# LED.net
KiCad netlist of a schematic drawn in Altium Designer
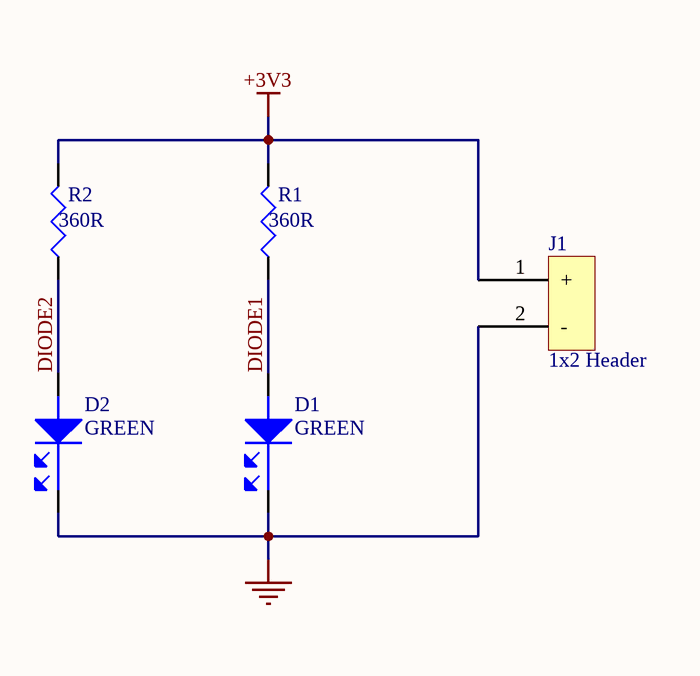
[diagram p0: LED.SchDoc]

(export (version "E")
  (design (tool "Eeschema 10.0.6"))
  (components
    (comp (ref "D1")
      (value "GREEN")
      (footprint "LED0603G")
      (description "Green 572nm LED Indication - Discrete 2V 0603 (1608 Metric)")
      (fields
        (field (name "MANUFACTURER") "Visual Communications")
        (field (name "MANUFACTURER PART NUMBER") "LSM0603453V")
      )
      (libsource (lib "LED_SchLib") (part "LSM0603453V"))
    )
    (comp (ref "D2")
      (value "GREEN")
      (footprint "LED0603G")
      (description "Green 572nm LED Indication - Discrete 2V 0603 (1608 Metric)")
      (fields
        (field (name "MANUFACTURER") "Visual Communications")
        (field (name "MANUFACTURER PART NUMBER") "LSM0603453V")
      )
      (libsource (lib "LED_SchLib") (part "LSM0603453V"))
    )
    (comp (ref "J1")
      (value "1x2 Header")
      (footprint "HDR1x2")
      (description "CONN HEADER VERT 2POS 2.54MM")
      (fields (field (name "MANUFACTURER") "Molex") (field (name "MANUFACTURER PART NUMBER") "22-27-2021"))
      (libsource (lib "LED_SchLib") (part "22-27-2021"))
    )
    (comp (ref "R1")
      (value "360R")
      (footprint "R0805")
      (description "RES SMD 360 OHM 1% 1/8W 0805")
      (fields
        (field (name "MANUFACTURER") "Yageo")
        (field (name "MANUFACTURER PART NUMBER") "AC0805FR-07360RL")
      )
      (libsource (lib "LED_SchLib") (part "AC0805FR-07360RL"))
    )
    (comp (ref "R2")
      (value "360R")
      (footprint "R0805")
      (description "RES SMD 360 OHM 1% 1/8W 0805")
      (fields
        (field (name "MANUFACTURER") "Yageo")
        (field (name "MANUFACTURER PART NUMBER") "AC0805FR-07360RL")
      )
      (libsource (lib "LED_SchLib") (part "AC0805FR-07360RL"))
    )
  )
  (nets
    (net (code "1") (name "+3V3") (class "Default")
      (node (ref "J1") (pin "1") (pinfunction "+_1") (pintype "passive"))
      (node (ref "R1") (pin "2") (pinfunction "2_2") (pintype "passive"))
      (node (ref "R2") (pin "2") (pinfunction "2_2") (pintype "passive"))
    )
    (net (code "2") (name "/DIODE1") (class "Default")
      (node (ref "D1") (pin "2") (pinfunction "2_2") (pintype "passive"))
      (node (ref "R1") (pin "1") (pinfunction "1_1") (pintype "passive"))
    )
    (net (code "3") (name "/DIODE2") (class "Default")
      (node (ref "D2") (pin "2") (pinfunction "2_2") (pintype "passive"))
      (node (ref "R2") (pin "1") (pinfunction "1_1") (pintype "passive"))
    )
    (net (code "4") (name "GND") (class "Default")
      (node (ref "D1") (pin "1") (pinfunction "1_1") (pintype "passive"))
      (node (ref "D2") (pin "1") (pinfunction "1_1") (pintype "passive"))
      (node (ref "J1") (pin "2") (pinfunction "-_2") (pintype "passive"))
    )
  )
)
